# finger_rev_1_3.net
KiCad netlist of a schematic drawn in EAGLE
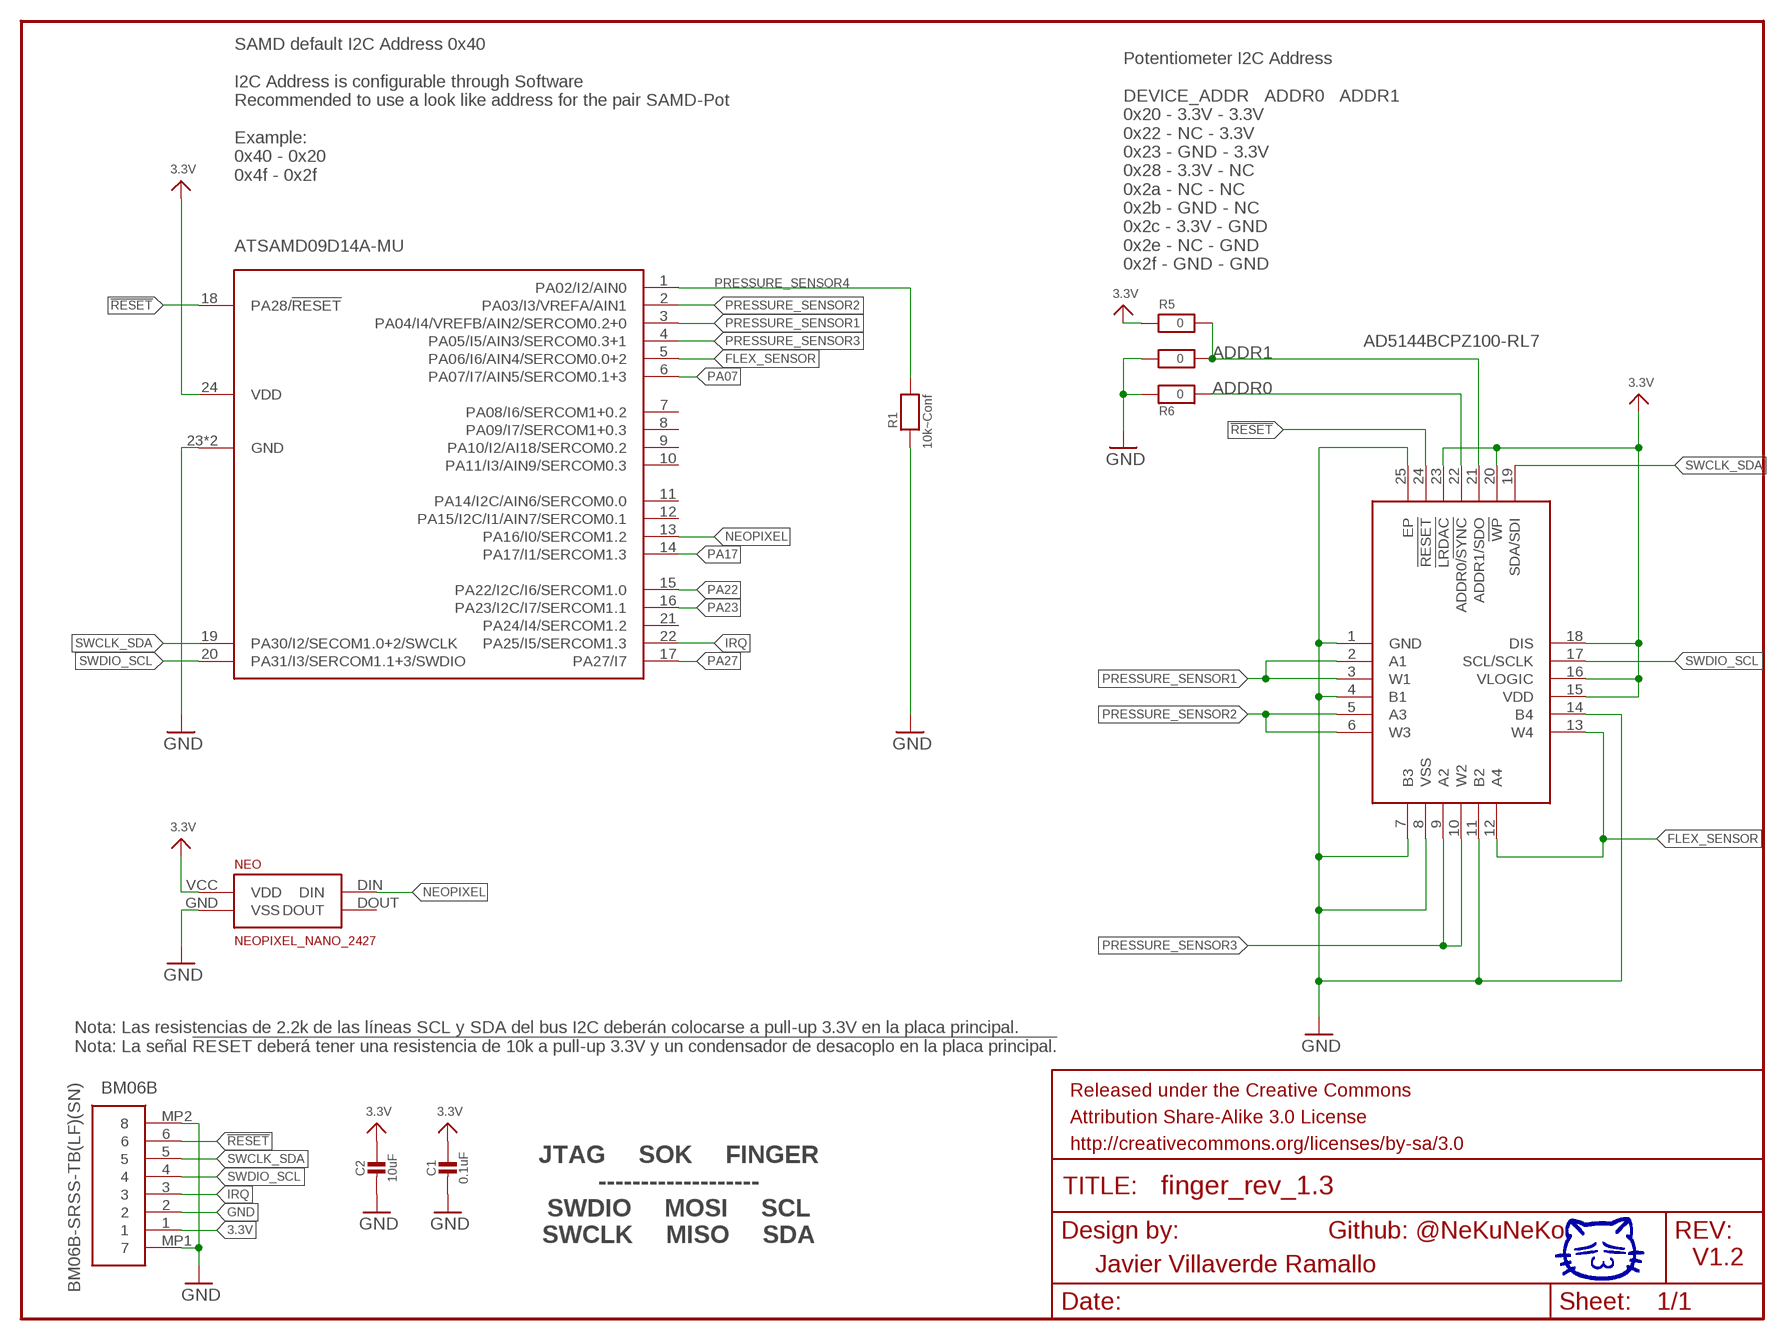
[diagram p0: schematic, sheet 1]

(export (version "E")
  (design (tool "Eeschema 10.0.6"))
  (components
    (comp (ref "AD5144BCPZ100")
      (value "AD5144BCPZ100-RL7")
      (footprint "eagle-import:QFN50P400X400X80-25N")
      (fields (field (name "MOUSER_PART_NUMBER") "584-AD5144BCPZ100-R7"))
      (libsource (lib "eagle-import") (part "AD5144BCPZ100-RL7"))
    )
    (comp (ref "BM06B")
      (value "BM06B-SRSS-TB(LF)(SN)")
      (footprint "eagle-import:BM06BSRSSTBLFSN")
      (fields (field (name "RS_PART_NUMBER") "5468782"))
      (libsource (lib "eagle-import") (part "BM06B-SRSS-TB(LF)(SN)"))
    )
    (comp (ref "C1")
      (value "0.1uF")
      (footprint "eagle-import:0402")
      (libsource (lib "eagle-import") (part "CAP_CERAMIC0402"))
    )
    (comp (ref "C2")
      (value "10uF")
      (footprint "eagle-import:0402")
      (libsource (lib "eagle-import") (part "CAP_CERAMIC0402"))
    )
    (comp (ref "FRAME1")
      (value "FRAME-LETTER")
      (footprint "eagle-import:CREATIVE_COMMONS")
      (libsource (lib "eagle-import") (part "FRAME-LETTER"))
    )
    (comp (ref "FRAME2")
      (value "FRAME-LETTER")
      (footprint "eagle-import:CREATIVE_COMMONS")
      (libsource (lib "eagle-import") (part "FRAME-LETTER"))
    )
    (comp (ref "NEO")
      (value "NEOPIXEL_NANO_2427")
      (footprint "eagle-import:SK6805-2427")
      (libsource (lib "eagle-import") (part "NEOPIXEL_NANO_2427"))
    )
    (comp (ref "R1")
      (value "10k~Conf")
      (footprint "eagle-import:_0402")
      (libsource (lib "eagle-import") (part "RESISTOR_0402"))
    )
    (comp (ref "R2")
      (value "0")
      (footprint "eagle-import:_0402")
      (libsource (lib "eagle-import") (part "RESISTOR_0402"))
    )
    (comp (ref "R5")
      (value "0")
      (footprint "eagle-import:_0402")
      (libsource (lib "eagle-import") (part "RESISTOR_0402"))
    )
    (comp (ref "R6")
      (value "0")
      (footprint "eagle-import:_0402")
      (libsource (lib "eagle-import") (part "RESISTOR_0402"))
    )
    (comp (ref "SAMD09")
      (value "ATSAMD09D14A-MU")
      (footprint "eagle-import:QFN24_4MM")
      (libsource (lib "eagle-import") (part "ATSAMD09D14A-MU"))
    )
  )
  (nets
    (net (code "1") (name "/ADDR0") (class "Default")
      (node (ref "AD5144BCPZ100") (pin "22") (pinfunction "ADDR0/~{SYNC}_22") (pintype "bidirectional"))
      (node (ref "R6") (pin "2") (pinfunction "2_2") (pintype "passive"))
    )
    (net (code "2") (name "/ADDR1") (class "Default")
      (node (ref "AD5144BCPZ100") (pin "21") (pinfunction "ADDR1/SDO_21") (pintype "bidirectional"))
      (node (ref "R2") (pin "2") (pinfunction "2_2") (pintype "passive"))
      (node (ref "R5") (pin "2") (pinfunction "2_2") (pintype "passive"))
    )
    (net (code "3") (name "/PRESSURE_SENSOR4") (class "Default")
      (node (ref "R1") (pin "1") (pinfunction "1_1") (pintype "passive"))
      (node (ref "SAMD09") (pin "1") (pinfunction "PA02/I2/AIN0_1") (pintype "bidirectional"))
    )
    (net (code "4") (name "/~{RESET}") (class "Default")
      (node (ref "AD5144BCPZ100") (pin "24") (pinfunction "~{RESET}_24") (pintype "bidirectional"))
      (node (ref "BM06B") (pin "6") (pinfunction "6_6") (pintype "bidirectional"))
      (node (ref "SAMD09") (pin "18") (pinfunction "PA28/~{RESET}_18") (pintype "bidirectional"))
    )
    (net (code "5") (name "3.3V") (class "Default")
      (node (ref "AD5144BCPZ100") (pin "15") (pinfunction "VDD_15") (pintype "bidirectional"))
      (node (ref "AD5144BCPZ100") (pin "16") (pinfunction "VLOGIC_16") (pintype "bidirectional"))
      (node (ref "AD5144BCPZ100") (pin "18") (pinfunction "DIS_18") (pintype "bidirectional"))
      (node (ref "AD5144BCPZ100") (pin "20") (pinfunction "~{WP}_20") (pintype "bidirectional"))
      (node (ref "AD5144BCPZ100") (pin "23") (pinfunction "~{LRDAC}_23") (pintype "bidirectional"))
      (node (ref "BM06B") (pin "1") (pinfunction "1_1") (pintype "bidirectional"))
      (node (ref "C1") (pin "1") (pinfunction "P$1_1") (pintype "passive"))
      (node (ref "C2") (pin "1") (pinfunction "P$1_1") (pintype "passive"))
      (node (ref "NEO") (pin "VCC") (pinfunction "VDD_VCC") (pintype "bidirectional"))
      (node (ref "R5") (pin "1") (pinfunction "1_1") (pintype "passive"))
      (node (ref "SAMD09") (pin "24") (pinfunction "VDD_24") (pintype "power_in"))
    )
    (net (code "6") (name "FLEX_SENSOR") (class "Default")
      (node (ref "AD5144BCPZ100") (pin "12") (pinfunction "A4_12") (pintype "bidirectional"))
      (node (ref "AD5144BCPZ100") (pin "13") (pinfunction "W4_13") (pintype "bidirectional"))
      (node (ref "SAMD09") (pin "5") (pinfunction "PA06/I6/AIN4/SERCOM0.0+2_5") (pintype "bidirectional"))
    )
    (net (code "7") (name "GND") (class "Default")
      (node (ref "AD5144BCPZ100") (pin "1") (pinfunction "GND_1") (pintype "bidirectional"))
      (node (ref "AD5144BCPZ100") (pin "11") (pinfunction "B2_11") (pintype "bidirectional"))
      (node (ref "AD5144BCPZ100") (pin "14") (pinfunction "B4_14") (pintype "bidirectional"))
      (node (ref "AD5144BCPZ100") (pin "25") (pinfunction "EP_25") (pintype "bidirectional"))
      (node (ref "AD5144BCPZ100") (pin "4") (pinfunction "B1_4") (pintype "bidirectional"))
      (node (ref "AD5144BCPZ100") (pin "7") (pinfunction "B3_7") (pintype "bidirectional"))
      (node (ref "AD5144BCPZ100") (pin "8") (pinfunction "VSS_8") (pintype "bidirectional"))
      (node (ref "BM06B") (pin "2") (pinfunction "2_2") (pintype "bidirectional"))
      (node (ref "BM06B") (pin "MP1") (pinfunction "7_MP1") (pintype "bidirectional"))
      (node (ref "BM06B") (pin "MP2") (pinfunction "8_MP2") (pintype "bidirectional"))
      (node (ref "C1") (pin "2") (pinfunction "P$2_2") (pintype "passive"))
      (node (ref "C2") (pin "2") (pinfunction "P$2_2") (pintype "passive"))
      (node (ref "NEO") (pin "GND") (pinfunction "VSS_GND") (pintype "bidirectional"))
      (node (ref "R1") (pin "2") (pinfunction "2_2") (pintype "passive"))
      (node (ref "R2") (pin "1") (pinfunction "1_1") (pintype "passive"))
      (node (ref "R6") (pin "1") (pinfunction "1_1") (pintype "passive"))
      (node (ref "SAMD09") (pin "23") (pinfunction "GND_23") (pintype "power_in"))
      (node (ref "SAMD09") (pin "THERM") (pinfunction "GND_THERM") (pintype "power_in"))
    )
    (net (code "8") (name "IRQ") (class "Default")
      (node (ref "BM06B") (pin "3") (pinfunction "3_3") (pintype "bidirectional"))
      (node (ref "SAMD09") (pin "22") (pinfunction "PA25/I5/SERCOM1.3_22") (pintype "bidirectional"))
    )
    (net (code "9") (name "NEOPIXEL") (class "Default")
      (node (ref "NEO") (pin "DIN") (pinfunction "DIN_DIN") (pintype "bidirectional"))
      (node (ref "SAMD09") (pin "13") (pinfunction "PA16/I0/SERCOM1.2_13") (pintype "bidirectional"))
    )
    (net (code "10") (name "PA07") (class "Default")
      (node (ref "SAMD09") (pin "6") (pinfunction "PA07/I7/AIN5/SERCOM0.1+3_6") (pintype "bidirectional"))
    )
    (net (code "11") (name "PA17") (class "Default")
      (node (ref "SAMD09") (pin "14") (pinfunction "PA17/I1/SERCOM1.3_14") (pintype "bidirectional"))
    )
    (net (code "12") (name "PA22") (class "Default")
      (node (ref "SAMD09") (pin "15") (pinfunction "PA22/I2C/I6/SERCOM1.0_15") (pintype "bidirectional"))
    )
    (net (code "13") (name "PA23") (class "Default")
      (node (ref "SAMD09") (pin "16") (pinfunction "PA23/I2C/I7/SERCOM1.1_16") (pintype "bidirectional"))
    )
    (net (code "14") (name "PA27") (class "Default")
      (node (ref "SAMD09") (pin "17") (pinfunction "PA27/I7_17") (pintype "bidirectional"))
    )
    (net (code "15") (name "PRESSURE_SENSOR1") (class "Default")
      (node (ref "AD5144BCPZ100") (pin "2") (pinfunction "A1_2") (pintype "bidirectional"))
      (node (ref "AD5144BCPZ100") (pin "3") (pinfunction "W1_3") (pintype "bidirectional"))
      (node (ref "SAMD09") (pin "3") (pinfunction "PA04/I4/VREFB/AIN2/SERCOM0.2+0_3") (pintype "bidirectional"))
    )
    (net (code "16") (name "PRESSURE_SENSOR2") (class "Default")
      (node (ref "AD5144BCPZ100") (pin "5") (pinfunction "A3_5") (pintype "bidirectional"))
      (node (ref "AD5144BCPZ100") (pin "6") (pinfunction "W3_6") (pintype "bidirectional"))
      (node (ref "SAMD09") (pin "2") (pinfunction "PA03/I3/VREFA/AIN1_2") (pintype "bidirectional"))
    )
    (net (code "17") (name "PRESSURE_SENSOR3") (class "Default")
      (node (ref "AD5144BCPZ100") (pin "10") (pinfunction "W2_10") (pintype "bidirectional"))
      (node (ref "AD5144BCPZ100") (pin "9") (pinfunction "A2_9") (pintype "bidirectional"))
      (node (ref "SAMD09") (pin "4") (pinfunction "PA05/I5/AIN3/SERCOM0.3+1_4") (pintype "bidirectional"))
    )
    (net (code "18") (name "SWCLK_SDA") (class "Default")
      (node (ref "AD5144BCPZ100") (pin "19") (pinfunction "SDA/SDI_19") (pintype "bidirectional"))
      (node (ref "BM06B") (pin "5") (pinfunction "5_5") (pintype "bidirectional"))
      (node (ref "SAMD09") (pin "19") (pinfunction "PA30/I2/SECOM1.0+2/SWCLK_19") (pintype "bidirectional"))
    )
    (net (code "19") (name "SWDIO_SCL") (class "Default")
      (node (ref "AD5144BCPZ100") (pin "17") (pinfunction "SCL/SCLK_17") (pintype "bidirectional"))
      (node (ref "BM06B") (pin "4") (pinfunction "4_4") (pintype "bidirectional"))
      (node (ref "SAMD09") (pin "20") (pinfunction "PA31/I3/SERCOM1.1+3/SWDIO_20") (pintype "bidirectional"))
    )
    (net (code "20") (name "unconnected-(NEO-PadDOUT)") (class "Default")
      (node (ref "NEO") (pin "DOUT") (pinfunction "DOUT_DOUT") (pintype "bidirectional"))
    )
    (net (code "21") (name "unconnected-(SAMD09-PA08{slash}I6{slash}SERCOM1+0.2-Pad7)") (class "Default")
      (node (ref "SAMD09") (pin "7") (pinfunction "PA08/I6/SERCOM1+0.2_7") (pintype "bidirectional"))
    )
    (net (code "22") (name "unconnected-(SAMD09-PA09{slash}I7{slash}SERCOM1+0.3-Pad8)") (class "Default")
      (node (ref "SAMD09") (pin "8") (pinfunction "PA09/I7/SERCOM1+0.3_8") (pintype "bidirectional"))
    )
    (net (code "23") (name "unconnected-(SAMD09-PA10{slash}I2{slash}AI18{slash}SERCOM0.2-Pad9)") (class "Default")
      (node (ref "SAMD09") (pin "9") (pinfunction "PA10/I2/AI18/SERCOM0.2_9") (pintype "bidirectional"))
    )
    (net (code "24") (name "unconnected-(SAMD09-PA11{slash}I3{slash}AIN9{slash}SERCOM0.3-Pad10)") (class "Default")
      (node (ref "SAMD09") (pin "10") (pinfunction "PA11/I3/AIN9/SERCOM0.3_10") (pintype "bidirectional"))
    )
    (net (code "25") (name "unconnected-(SAMD09-PA14{slash}I2C{slash}AIN6{slash}SERCOM0.0-Pad11)") (class "Default")
      (node (ref "SAMD09") (pin "11") (pinfunction "PA14/I2C/AIN6/SERCOM0.0_11") (pintype "bidirectional"))
    )
    (net (code "26") (name "unconnected-(SAMD09-PA15{slash}I2C{slash}I1{slash}AIN7{slash}SERCOM0.1-Pad12)") (class "Default")
      (node (ref "SAMD09") (pin "12") (pinfunction "PA15/I2C/I1/AIN7/SERCOM0.1_12") (pintype "bidirectional"))
    )
    (net (code "27") (name "unconnected-(SAMD09-PA24{slash}I4{slash}SERCOM1.2-Pad21)") (class "Default")
      (node (ref "SAMD09") (pin "21") (pinfunction "PA24/I4/SERCOM1.2_21") (pintype "bidirectional"))
    )
  )
)
